# usb_c_connection.net
KiCad netlist of a schematic drawn in Altium Designer
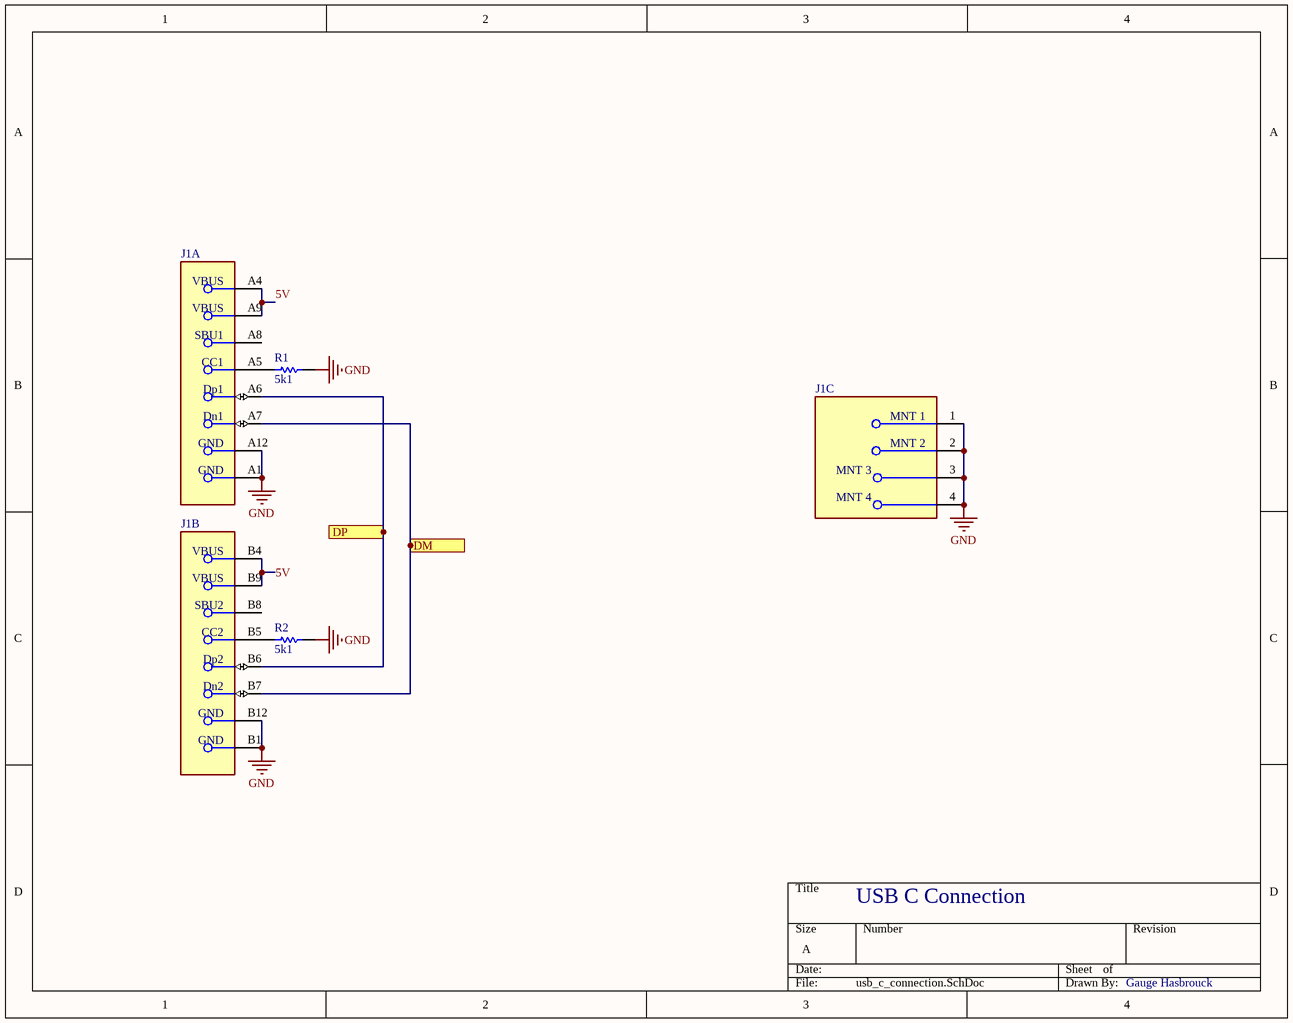
[diagram p0: usb_c_connection.SchDoc]

(export (version "E")
  (design (tool "Eeschema 10.0.6"))
  (components
    (comp (ref "J1")
      (value "213716-0001")
      (footprint "FP-213716-0001-MFG")
      (description "CONN RCPT USB2.0 TYPE C 24POS RA")
      (libsource (lib "Altium Content Vault") (part "d371042584e5ad1ff312aac3cd0a0ad"))
    )
    (comp (ref "R1")
      (value "5k1")
      (footprint "RESC1005X40X25NL05T10")
      (fields (field (name "PART NUMBER") "RC0402FR-075K1L") (field (name "MANUFACTURER") "Yageo / Phycomp"))
      (libsource (lib "Altium Content Vault") (part "RES"))
    )
    (comp (ref "R2")
      (value "5k1")
      (footprint "RESC1005X40X25NL05T10")
      (fields (field (name "PART NUMBER") "RC0402FR-075K1L") (field (name "MANUFACTURER") "Yageo / Phycomp"))
      (libsource (lib "Altium Content Vault") (part "RES"))
    )
  )
  (nets
    (net (code "1") (name "/5V") (class "Default")
      (node (ref "J1") (pin "A4") (pinfunction "VBUS_A4") (pintype "power_in"))
      (node (ref "J1") (pin "A9") (pinfunction "VBUS_A9") (pintype "power_in"))
      (node (ref "J1") (pin "B4") (pinfunction "VBUS_B4") (pintype "power_in"))
      (node (ref "J1") (pin "B9") (pinfunction "VBUS_B9") (pintype "power_in"))
    )
    (net (code "2") (name "/DM") (class "Default")
      (node (ref "J1") (pin "A7") (pinfunction "Dn1_A7") (pintype "bidirectional"))
      (node (ref "J1") (pin "B7") (pinfunction "Dn2_B7") (pintype "bidirectional"))
    )
    (net (code "3") (name "/DP") (class "Default")
      (node (ref "J1") (pin "A6") (pinfunction "Dp1_A6") (pintype "bidirectional"))
      (node (ref "J1") (pin "B6") (pinfunction "Dp2_B6") (pintype "bidirectional"))
    )
    (net (code "4") (name "GND") (class "Default")
      (node (ref "J1") (pin "1") (pinfunction "MNT_1_1") (pintype "passive"))
      (node (ref "J1") (pin "2") (pinfunction "MNT_2_2") (pintype "passive"))
      (node (ref "J1") (pin "3") (pinfunction "MNT_3_3") (pintype "passive"))
      (node (ref "J1") (pin "4") (pinfunction "MNT_4_4") (pintype "passive"))
      (node (ref "J1") (pin "A1") (pinfunction "GND_A1") (pintype "power_in"))
      (node (ref "J1") (pin "A12") (pinfunction "GND_A12") (pintype "power_in"))
      (node (ref "J1") (pin "B1") (pinfunction "GND_B1") (pintype "power_in"))
      (node (ref "J1") (pin "B12") (pinfunction "GND_B12") (pintype "power_in"))
      (node (ref "R1") (pin "2") (pinfunction "2_2") (pintype "passive"))
      (node (ref "R2") (pin "2") (pinfunction "2_2") (pintype "passive"))
    )
    (net (code "5") (name "Net-(J1A-CC1)") (class "Default")
      (node (ref "J1") (pin "A5") (pinfunction "CC1_A5") (pintype "passive"))
      (node (ref "R1") (pin "1") (pinfunction "1_1") (pintype "passive"))
    )
    (net (code "6") (name "Net-(J1B-CC2)") (class "Default")
      (node (ref "J1") (pin "B5") (pinfunction "CC2_B5") (pintype "passive"))
      (node (ref "R2") (pin "1") (pinfunction "1_1") (pintype "passive"))
    )
    (net (code "7") (name "unconnected-(J1A-SBU1-PadA8)") (class "Default")
      (node (ref "J1") (pin "A8") (pinfunction "SBU1_A8") (pintype "passive"))
    )
    (net (code "8") (name "unconnected-(J1B-SBU2-PadB8)") (class "Default")
      (node (ref "J1") (pin "B8") (pinfunction "SBU2_B8") (pintype "passive"))
    )
  )
)
